# AAS_module_Power-rev1_2.net
KiCad netlist of a schematic drawn in Altium Designer
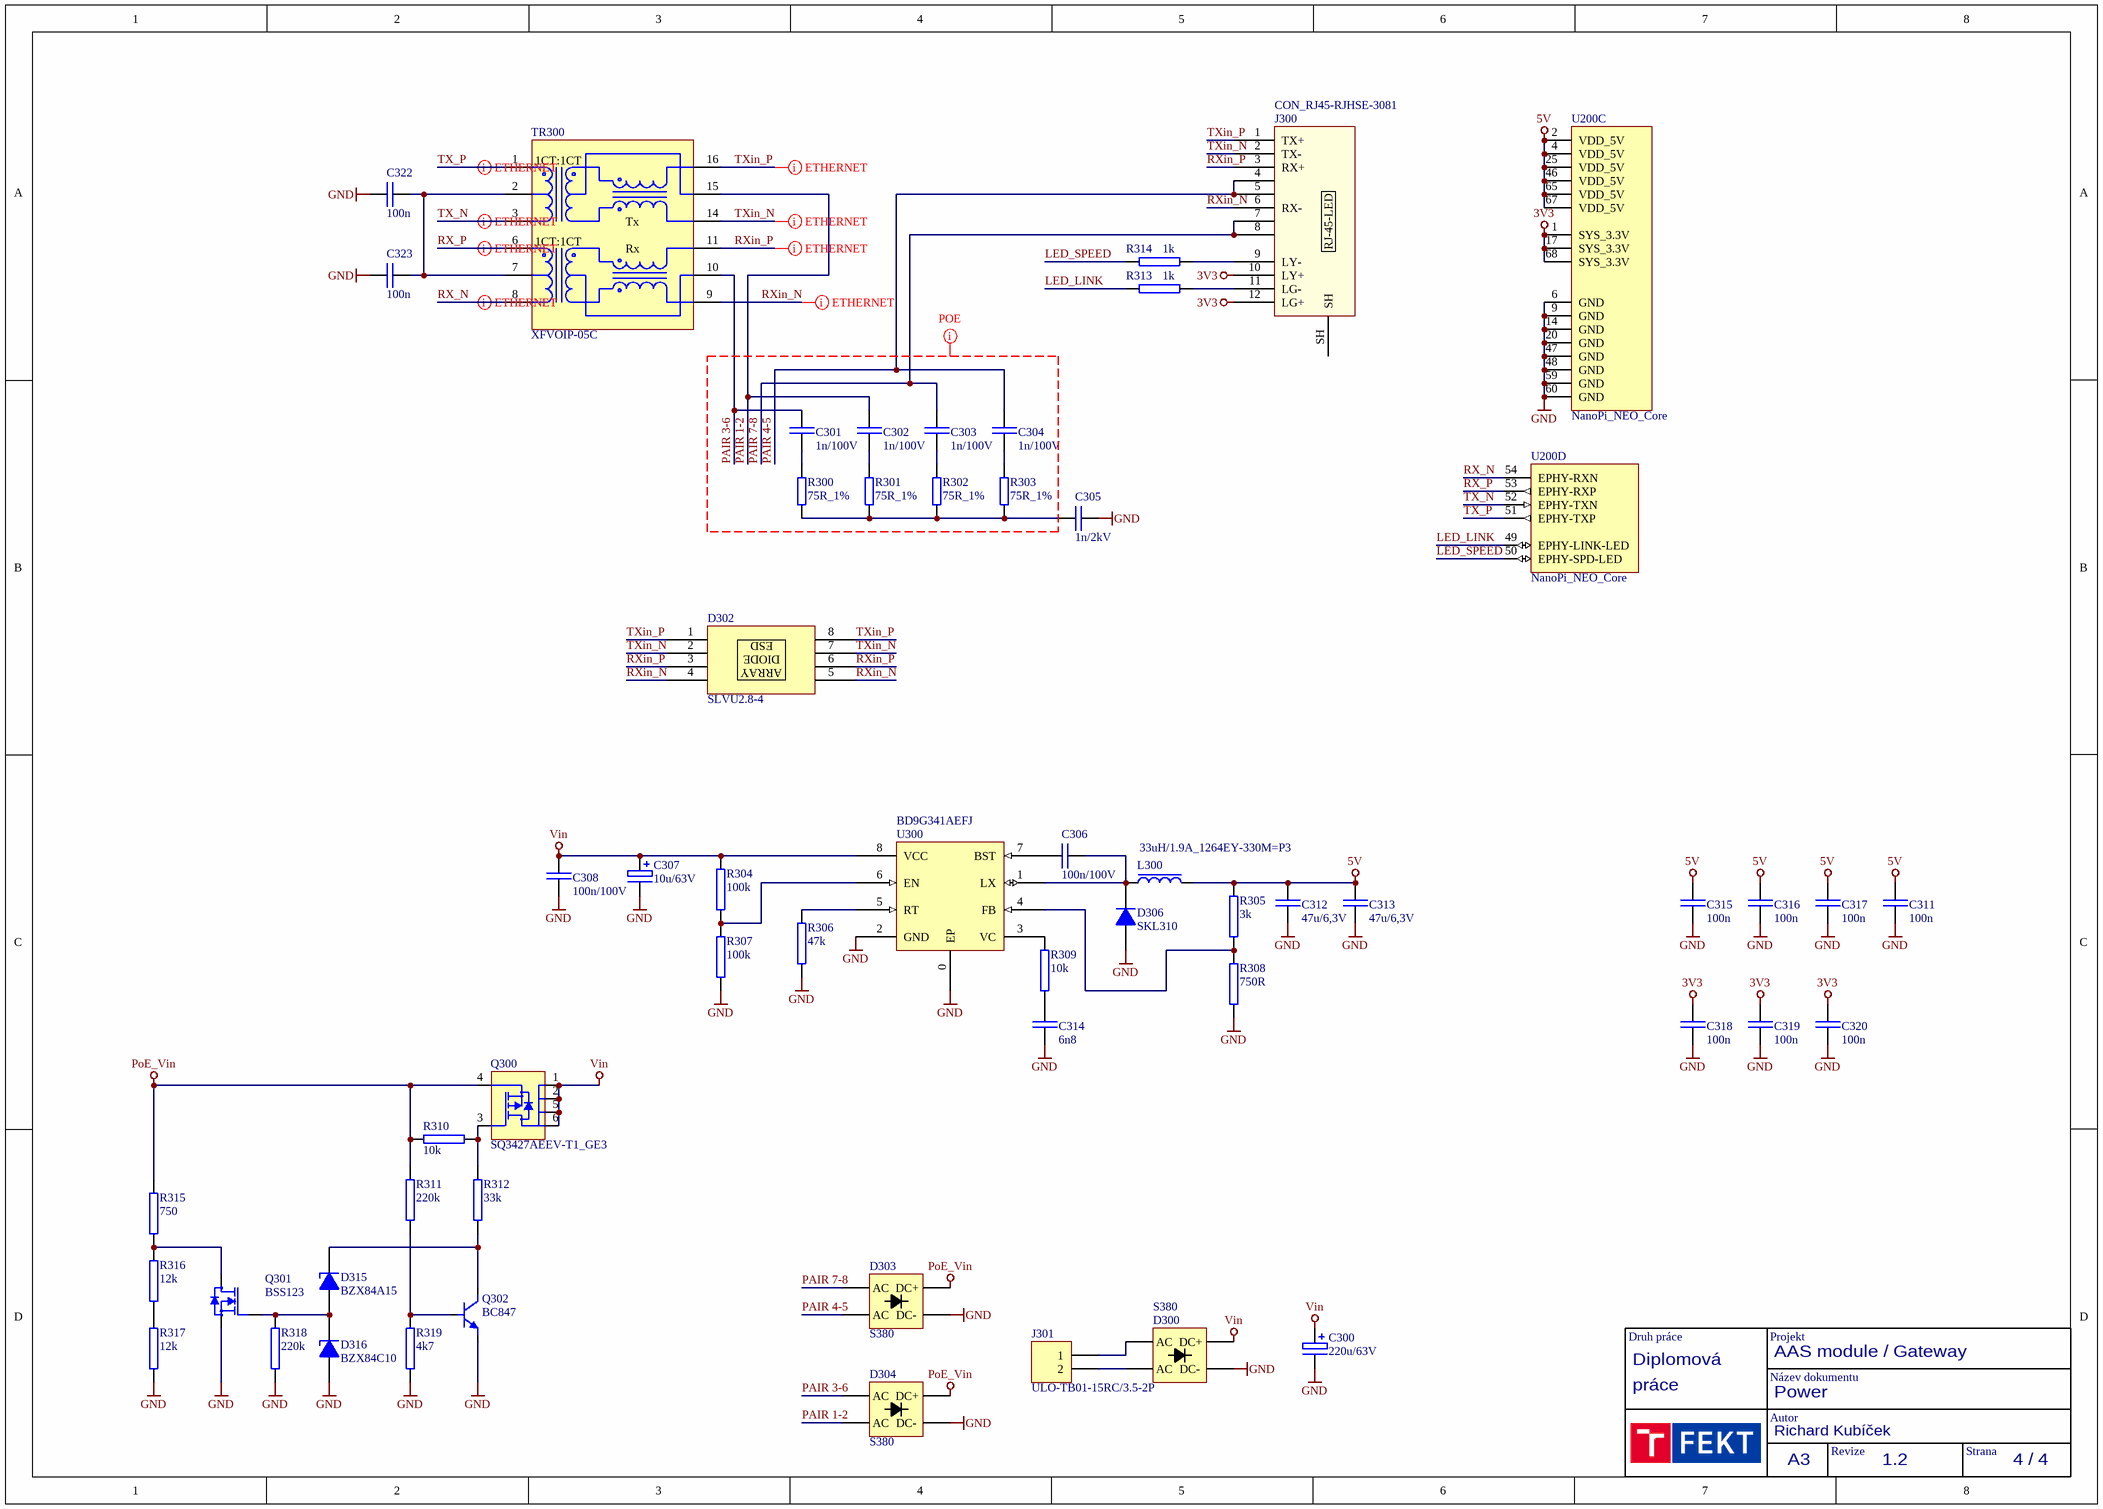
[diagram p0: AAS_module_Power-rev1_2.SchDoc]

(export (version "E")
  (design (tool "Eeschema 10.0.6"))
  (components
    (comp (ref "C300")
      (value "220u/63V")
      (footprint "CAP_D10xL20_P5_HR")
      (description "Electrolytic Capacitor")
      (libsource (lib "my_parts") (part "C_ELYT"))
    )
    (comp (ref "C301")
      (value "1n/100V")
      (footprint "C0603")
      (description "Capacitor SMD 0603")
      (libsource (lib "SmartSys") (part "C_0603"))
    )
    (comp (ref "C302")
      (value "1n/100V")
      (footprint "C0603")
      (description "Capacitor SMD 0603")
      (libsource (lib "SmartSys") (part "C_0603"))
    )
    (comp (ref "C303")
      (value "1n/100V")
      (footprint "C0603")
      (description "Capacitor SMD 0603")
      (libsource (lib "SmartSys") (part "C_0603"))
    )
    (comp (ref "C304")
      (value "1n/100V")
      (footprint "C0603")
      (description "Capacitor SMD 0603")
      (libsource (lib "SmartSys") (part "C_0603"))
    )
    (comp (ref "C305")
      (value "1n/2kV")
      (footprint "C1206")
      (description "Capacitor SMD 1206")
      (libsource (lib "SmartSys") (part "C_1206"))
    )
    (comp (ref "C306")
      (value "100n/100V")
      (footprint "C1206")
      (description "Capacitor SMD 1206")
      (libsource (lib "SmartSys") (part "C_1206"))
    )
    (comp (ref "C307")
      (value "10u/63V")
      (footprint "C_ALU_D6x5.8")
      (description "Electrolytic Aluminium Capacitor")
      (libsource (lib "SmartSys") (part "C_ALU"))
    )
    (comp (ref "C308")
      (value "100n/100V")
      (footprint "C1206")
      (description "Capacitor SMD 1206")
      (libsource (lib "SmartSys") (part "C_1206"))
    )
    (comp (ref "C311")
      (value "100n")
      (footprint "C0603")
      (description "Capacitor SMD 0603")
      (libsource (lib "SmartSys") (part "C_0603"))
    )
    (comp (ref "C312")
      (value "47u/6,3V")
      (footprint "C1206")
      (description "Capacitor SMD 1206")
      (libsource (lib "SmartSys") (part "C_1206"))
    )
    (comp (ref "C313")
      (value "47u/6,3V")
      (footprint "C1206")
      (description "Capacitor SMD 1206")
      (libsource (lib "SmartSys") (part "C_1206"))
    )
    (comp (ref "C314")
      (value "6n8")
      (footprint "C0805")
      (description "Capacitor SMD 0805")
      (libsource (lib "SmartSys") (part "C_0805"))
    )
    (comp (ref "C315")
      (value "100n")
      (footprint "C0603")
      (description "Capacitor SMD 0603")
      (libsource (lib "SmartSys") (part "C_0603"))
    )
    (comp (ref "C316")
      (value "100n")
      (footprint "C0603")
      (description "Capacitor SMD 0603")
      (libsource (lib "SmartSys") (part "C_0603"))
    )
    (comp (ref "C317")
      (value "100n")
      (footprint "C0603")
      (description "Capacitor SMD 0603")
      (libsource (lib "SmartSys") (part "C_0603"))
    )
    (comp (ref "C318")
      (value "100n")
      (footprint "C0603")
      (description "Capacitor SMD 0603")
      (libsource (lib "SmartSys") (part "C_0603"))
    )
    (comp (ref "C319")
      (value "100n")
      (footprint "C0603")
      (description "Capacitor SMD 0603")
      (libsource (lib "SmartSys") (part "C_0603"))
    )
    (comp (ref "C320")
      (value "100n")
      (footprint "C0603")
      (description "Capacitor SMD 0603")
      (libsource (lib "SmartSys") (part "C_0603"))
    )
    (comp (ref "C322")
      (value "100n")
      (footprint "C0603")
      (description "Capacitor SMD 0603")
      (libsource (lib "SmartSys") (part "C_0603"))
    )
    (comp (ref "C323")
      (value "100n")
      (footprint "C0603")
      (description "Capacitor SMD 0603")
      (libsource (lib "SmartSys") (part "C_0603"))
    )
    (comp (ref "D300")
      (value "S380")
      (footprint "MBS")
      (description "Diode rectifier")
      (libsource (lib "SmartSys") (part "_DIODE_BRIDGE_RECTIFIER"))
    )
    (comp (ref "D302")
      (value "SLVU2.8-4")
      (footprint "SO-8")
      (description "EPD TVS Diode Array  For ESD and Latch-Up Protection")
      (libsource (lib "SmartSys") (part "SLVU2.8-4"))
    )
    (comp (ref "D303")
      (value "S380")
      (footprint "MBS")
      (description "Diode rectifier")
      (libsource (lib "SmartSys") (part "_DIODE_BRIDGE_RECTIFIER"))
    )
    (comp (ref "D304")
      (value "S380")
      (footprint "MBS")
      (description "Diode rectifier")
      (libsource (lib "SmartSys") (part "_DIODE_BRIDGE_RECTIFIER"))
    )
    (comp (ref "D306")
      (value "SKL310")
      (footprint "SOD123")
      (description "Diode")
      (libsource (lib "SmartSys") (part "1N4007"))
    )
    (comp (ref "D315")
      (value "BZX84A15")
      (footprint "SOT-23")
      (description "Zener diode")
      (libsource (lib "SmartSys") (part "BZX84CXXX"))
    )
    (comp (ref "D316")
      (value "BZX84C10")
      (footprint "SOT-23")
      (description "Zener diode")
      (libsource (lib "SmartSys") (part "BZX84CXXX"))
    )
    (comp (ref "J300")
      (value "CON_RJ45-RJHSE-3081")
      (footprint "RJHSE-3081")
      (libsource (lib "my_parts") (part "CON_RJ45-LED_DESCRIPTION"))
    )
    (comp (ref "J301")
      (value "ULO-TB01-15RC/3.5-2P")
      (footprint "ULO-TB01-15VC-3.5-2P")
      (description "Connector 15EDG pitch 3.5mm Right Angle")
      (libsource (lib "SmartSys") (part "CON_ULO-TB01-15RC/3.5-2P"))
    )
    (comp (ref "L300")
      (value "33uH/1.9A_1264EY-330M=P3")
      (footprint "L_MURATA-DG6050C")
      (libsource (lib "ELEKON") (part "INDUCTOR"))
    )
    (comp (ref "Q300")
      (value "SQ3427AEEV-T1_GE3")
      (footprint "SOT-23-6")
      (libsource (lib "ELEKON") (part "SQ3419EV"))
    )
    (comp (ref "Q301")
      (value "BSS123")
      (footprint "SOT-23")
      (description "N-Channel MOSFET")
      (libsource (lib "SmartSys") (part "BSS138"))
    )
    (comp (ref "Q302")
      (value "BC847")
      (footprint "SOT-23")
      (description "NPN Transistor")
      (libsource (lib "SmartSys") (part "BC847"))
    )
    (comp (ref "R300")
      (value "75R_1%")
      (footprint "R_0805")
      (fields (field (name "TOLERANCE") "1"))
      (libsource (lib "ELEKON") (part "Resistor"))
    )
    (comp (ref "R301")
      (value "75R_1%")
      (footprint "R_0805")
      (fields (field (name "TOLERANCE") "1"))
      (libsource (lib "ELEKON") (part "Resistor"))
    )
    (comp (ref "R302")
      (value "75R_1%")
      (footprint "R_0805")
      (fields (field (name "TOLERANCE") "1"))
      (libsource (lib "ELEKON") (part "Resistor"))
    )
    (comp (ref "R303")
      (value "75R_1%")
      (footprint "R_0805")
      (fields (field (name "TOLERANCE") "1"))
      (libsource (lib "ELEKON") (part "Resistor"))
    )
    (comp (ref "R304")
      (value "100k")
      (footprint "R0603")
      (description "Resistor SMD 0603")
      (libsource (lib "SmartSys") (part "R_0603"))
    )
    (comp (ref "R305")
      (value "3k")
      (footprint "R0603")
      (description "Resistor SMD 0603")
      (libsource (lib "SmartSys") (part "R_0603"))
    )
    (comp (ref "R306")
      (value "47k")
      (footprint "R0603")
      (description "Resistor SMD 0603")
      (libsource (lib "SmartSys") (part "R_0603"))
    )
    (comp (ref "R307")
      (value "100k")
      (footprint "R0603")
      (description "Resistor SMD 0603")
      (libsource (lib "SmartSys") (part "R_0603"))
    )
    (comp (ref "R308")
      (value "750R")
      (footprint "R0603")
      (description "Resistor SMD 0603")
      (libsource (lib "SmartSys") (part "R_0603"))
    )
    (comp (ref "R309")
      (value "10k")
      (footprint "R0603")
      (description "Resistor SMD 0603")
      (libsource (lib "SmartSys") (part "R_0603"))
    )
    (comp (ref "R310")
      (value "10k")
      (footprint "R0603")
      (description "Resistor SMD 0603")
      (libsource (lib "SmartSys") (part "R_0603"))
    )
    (comp (ref "R311")
      (value "220k")
      (footprint "R0603")
      (description "Resistor SMD 0603")
      (libsource (lib "SmartSys") (part "R_0603"))
    )
    (comp (ref "R312")
      (value "33k")
      (footprint "R0603")
      (description "Resistor SMD 0603")
      (libsource (lib "SmartSys") (part "R_0603"))
    )
    (comp (ref "R313")
      (value "1k")
      (footprint "R0603")
      (description "Resistor SMD 0603")
      (libsource (lib "SmartSys") (part "R_0603"))
    )
    (comp (ref "R314")
      (value "1k")
      (footprint "R0603")
      (description "Resistor SMD 0603")
      (libsource (lib "SmartSys") (part "R_0603"))
    )
    (comp (ref "R315")
      (value "750")
      (footprint "R0603")
      (description "Resistor SMD 0603")
      (libsource (lib "SmartSys") (part "R_0603"))
    )
    (comp (ref "R316")
      (value "12k")
      (footprint "R0603")
      (description "Resistor SMD 0603")
      (libsource (lib "SmartSys") (part "R_0603"))
    )
    (comp (ref "R317")
      (value "12k")
      (footprint "R0603")
      (description "Resistor SMD 0603")
      (libsource (lib "SmartSys") (part "R_0603"))
    )
    (comp (ref "R318")
      (value "220k")
      (footprint "R0603")
      (description "Resistor SMD 0603")
      (libsource (lib "SmartSys") (part "R_0603"))
    )
    (comp (ref "R319")
      (value "4k7")
      (footprint "R0603")
      (description "Resistor SMD 0603")
      (libsource (lib "SmartSys") (part "R_0603"))
    )
    (comp (ref "TR300")
      (value "XFVOIP-05C")
      (footprint "XFVOIP-05")
      (description "LAN magnetics with filter")
      (libsource (lib "my_parts") (part "XFVOIP-05"))
    )
    (comp (ref "U200")
      (value "NanoPi_NEO_Core")
      (footprint "NanoPi_NEO_Core_right")
      (libsource (lib "my_parts") (part "NanoPi_NEO_Core"))
    )
    (comp (ref "U300")
      (value "BD9G341AEFJ")
      (footprint "SO-8_EP")
      (description "12V to 76V input voltage range 3A output current")
      (libsource (lib "my_parts") (part "BD9G341AEFJ"))
    )
  )
  (nets
    (net (code "1") (name "/LED_LINK") (class "Default")
      (node (ref "R313") (pin "2") (pinfunction "2_2") (pintype "passive"))
      (node (ref "U200") (pin "49") (pinfunction "EPHY-LINK-LED_49") (pintype "bidirectional"))
    )
    (net (code "2") (name "/LED_SPEED") (class "Default")
      (node (ref "R314") (pin "2") (pinfunction "2_2") (pintype "passive"))
      (node (ref "U200") (pin "50") (pinfunction "EPHY-SPD-LED_50") (pintype "bidirectional"))
    )
    (net (code "3") (name "/PAIR 1-2") (class "Default")
      (node (ref "C302") (pin "1") (pinfunction "1_1") (pintype "passive"))
      (node (ref "D304") (pin "4") (pinfunction "AC_4") (pintype "passive"))
      (node (ref "TR300") (pin "15") (pinfunction "TXCT_15") (pintype "passive"))
    )
    (net (code "4") (name "/PAIR 3-6") (class "Default")
      (node (ref "C301") (pin "1") (pinfunction "1_1") (pintype "passive"))
      (node (ref "D304") (pin "3") (pinfunction "AC_3") (pintype "passive"))
      (node (ref "TR300") (pin "10") (pinfunction "RXCT_10") (pintype "passive"))
    )
    (net (code "5") (name "/PAIR 4-5") (class "Default")
      (node (ref "C304") (pin "1") (pinfunction "1_1") (pintype "passive"))
      (node (ref "D303") (pin "4") (pinfunction "AC_4") (pintype "passive"))
      (node (ref "J300") (pin "4") (pintype "passive"))
      (node (ref "J300") (pin "5") (pintype "passive"))
    )
    (net (code "6") (name "/PAIR 7-8") (class "Default")
      (node (ref "C303") (pin "1") (pinfunction "1_1") (pintype "passive"))
      (node (ref "D303") (pin "3") (pinfunction "AC_3") (pintype "passive"))
      (node (ref "J300") (pin "7") (pintype "passive"))
      (node (ref "J300") (pin "8") (pintype "passive"))
    )
    (net (code "7") (name "/RX_N") (class "Default")
      (node (ref "TR300") (pin "8") (pinfunction "RD-_8") (pintype "passive"))
      (node (ref "U200") (pin "54") (pinfunction "EPHY-RXN_54") (pintype "passive"))
    )
    (net (code "8") (name "/RX_P") (class "Default")
      (node (ref "TR300") (pin "6") (pinfunction "RD+_6") (pintype "passive"))
      (node (ref "U200") (pin "53") (pinfunction "EPHY-RXP_53") (pintype "output"))
    )
    (net (code "9") (name "/RXin_N") (class "Default")
      (node (ref "D302") (pin "4") (pinfunction "4_4") (pintype "passive"))
      (node (ref "D302") (pin "5") (pinfunction "5_5") (pintype "passive"))
      (node (ref "J300") (pin "6") (pinfunction "RX-_6") (pintype "passive"))
      (node (ref "TR300") (pin "9") (pinfunction "RX1-_9") (pintype "passive"))
    )
    (net (code "10") (name "/RXin_P") (class "Default")
      (node (ref "D302") (pin "3") (pinfunction "3_3") (pintype "passive"))
      (node (ref "D302") (pin "6") (pinfunction "6_6") (pintype "passive"))
      (node (ref "J300") (pin "3") (pinfunction "RX+_3") (pintype "passive"))
      (node (ref "TR300") (pin "11") (pinfunction "RX1+_11") (pintype "passive"))
    )
    (net (code "11") (name "/TX_N") (class "Default")
      (node (ref "TR300") (pin "3") (pinfunction "TD-_3") (pintype "passive"))
      (node (ref "U200") (pin "52") (pinfunction "EPHY-TXN_52") (pintype "input"))
    )
    (net (code "12") (name "/TX_P") (class "Default")
      (node (ref "TR300") (pin "1") (pinfunction "TD+_1") (pintype "passive"))
      (node (ref "U200") (pin "51") (pinfunction "EPHY-TXP_51") (pintype "output"))
    )
    (net (code "13") (name "/TXin_N") (class "Default")
      (node (ref "D302") (pin "2") (pinfunction "2_2") (pintype "passive"))
      (node (ref "D302") (pin "7") (pinfunction "7_7") (pintype "passive"))
      (node (ref "J300") (pin "2") (pinfunction "TX-_2") (pintype "passive"))
      (node (ref "TR300") (pin "14") (pinfunction "TX1-_14") (pintype "passive"))
    )
    (net (code "14") (name "/TXin_P") (class "Default")
      (node (ref "D302") (pin "1") (pinfunction "1_1") (pintype "passive"))
      (node (ref "D302") (pin "8") (pinfunction "8_8") (pintype "passive"))
      (node (ref "J300") (pin "1") (pinfunction "TX+_1") (pintype "passive"))
      (node (ref "TR300") (pin "16") (pinfunction "TX1+_16") (pintype "passive"))
    )
    (net (code "15") (name "3V3") (class "Default")
      (node (ref "C318") (pin "1") (pinfunction "1_1") (pintype "passive"))
      (node (ref "C319") (pin "1") (pinfunction "1_1") (pintype "passive"))
      (node (ref "C320") (pin "1") (pinfunction "1_1") (pintype "passive"))
      (node (ref "J300") (pin "10") (pinfunction "LY+_10") (pintype "passive"))
      (node (ref "J300") (pin "12") (pinfunction "LG+_12") (pintype "passive"))
      (node (ref "U200") (pin "1") (pinfunction "SYS_3.3V_1") (pintype "power_in"))
      (node (ref "U200") (pin "17") (pinfunction "SYS_3.3V_17") (pintype "power_in"))
      (node (ref "U200") (pin "68") (pinfunction "SYS_3.3V_68") (pintype "power_in"))
    )
    (net (code "16") (name "5V") (class "Default")
      (node (ref "C311") (pin "1") (pinfunction "1_1") (pintype "passive"))
      (node (ref "C312") (pin "1") (pinfunction "1_1") (pintype "passive"))
      (node (ref "C313") (pin "1") (pinfunction "1_1") (pintype "passive"))
      (node (ref "C315") (pin "1") (pinfunction "1_1") (pintype "passive"))
      (node (ref "C316") (pin "1") (pinfunction "1_1") (pintype "passive"))
      (node (ref "C317") (pin "1") (pinfunction "1_1") (pintype "passive"))
      (node (ref "L300") (pin "2") (pinfunction "2_2") (pintype "passive"))
      (node (ref "R305") (pin "2") (pinfunction "2_2") (pintype "passive"))
      (node (ref "U200") (pin "2") (pinfunction "VDD_5V_2") (pintype "power_in"))
      (node (ref "U200") (pin "25") (pinfunction "VDD_5V_25") (pintype "power_in"))
      (node (ref "U200") (pin "4") (pinfunction "VDD_5V_4") (pintype "power_in"))
      (node (ref "U200") (pin "46") (pinfunction "VDD_5V_46") (pintype "power_in"))
      (node (ref "U200") (pin "65") (pinfunction "VDD_5V_65") (pintype "power_in"))
      (node (ref "U200") (pin "67") (pinfunction "VDD_5V_67") (pintype "power_in"))
    )
    (net (code "17") (name "GND") (class "Default")
      (node (ref "C300") (pin "2") (pinfunction "-_2") (pintype "passive"))
      (node (ref "C305") (pin "2") (pinfunction "2_2") (pintype "passive"))
      (node (ref "C307") (pin "2") (pinfunction "-_2") (pintype "passive"))
      (node (ref "C308") (pin "2") (pinfunction "2_2") (pintype "passive"))
      (node (ref "C311") (pin "2") (pinfunction "2_2") (pintype "passive"))
      (node (ref "C312") (pin "2") (pinfunction "2_2") (pintype "passive"))
      (node (ref "C313") (pin "2") (pinfunction "2_2") (pintype "passive"))
      (node (ref "C314") (pin "1") (pinfunction "1_1") (pintype "passive"))
      (node (ref "C315") (pin "2") (pinfunction "2_2") (pintype "passive"))
      (node (ref "C316") (pin "2") (pinfunction "2_2") (pintype "passive"))
      (node (ref "C317") (pin "2") (pinfunction "2_2") (pintype "passive"))
      (node (ref "C318") (pin "2") (pinfunction "2_2") (pintype "passive"))
      (node (ref "C319") (pin "2") (pinfunction "2_2") (pintype "passive"))
      (node (ref "C320") (pin "2") (pinfunction "2_2") (pintype "passive"))
      (node (ref "C322") (pin "1") (pinfunction "1_1") (pintype "passive"))
      (node (ref "C323") (pin "1") (pinfunction "1_1") (pintype "passive"))
      (node (ref "D300") (pin "2") (pinfunction "DC-_2") (pintype "passive"))
      (node (ref "D303") (pin "2") (pinfunction "DC-_2") (pintype "passive"))
      (node (ref "D304") (pin "2") (pinfunction "DC-_2") (pintype "passive"))
      (node (ref "D306") (pin "A") (pinfunction "A_A") (pintype "passive"))
      (node (ref "D316") (pin "A") (pinfunction "A_A") (pintype "passive"))
      (node (ref "Q301") (pin "S") (pinfunction "S_S") (pintype "passive"))
      (node (ref "Q302") (pin "E") (pinfunction "E_E") (pintype "passive"))
      (node (ref "R306") (pin "1") (pinfunction "1_1") (pintype "passive"))
      (node (ref "R307") (pin "1") (pinfunction "1_1") (pintype "passive"))
      (node (ref "R308") (pin "1") (pinfunction "1_1") (pintype "passive"))
      (node (ref "R317") (pin "1") (pinfunction "1_1") (pintype "passive"))
      (node (ref "R318") (pin "1") (pinfunction "1_1") (pintype "passive"))
      (node (ref "R319") (pin "1") (pinfunction "1_1") (pintype "passive"))
      (node (ref "U200") (pin "14") (pinfunction "GND_14") (pintype "power_in"))
      (node (ref "U200") (pin "20") (pinfunction "GND_20") (pintype "power_in"))
      (node (ref "U200") (pin "47") (pinfunction "GND_47") (pintype "power_in"))
      (node (ref "U200") (pin "48") (pinfunction "GND_48") (pintype "power_in"))
      (node (ref "U200") (pin "59") (pinfunction "GND_59") (pintype "power_in"))
      (node (ref "U200") (pin "6") (pinfunction "GND_6") (pintype "power_in"))
      (node (ref "U200") (pin "60") (pinfunction "GND_60") (pintype "power_in"))
      (node (ref "U200") (pin "9") (pinfunction "GND_9") (pintype "power_in"))
      (node (ref "U300") (pin "0") (pinfunction "EP_0") (pintype "passive"))
      (node (ref "U300") (pin "2") (pinfunction "GND_2") (pintype "passive"))
    )
    (net (code "18") (name "Net-(C301-Pad2)") (class "Default")
      (node (ref "C301") (pin "2") (pinfunction "2_2") (pintype "passive"))
      (node (ref "R300") (pin "2") (pinfunction "2_2") (pintype "passive"))
    )
    (net (code "19") (name "Net-(C302-Pad2)") (class "Default")
      (node (ref "C302") (pin "2") (pinfunction "2_2") (pintype "passive"))
      (node (ref "R301") (pin "2") (pinfunction "2_2") (pintype "passive"))
    )
    (net (code "20") (name "Net-(C303-Pad2)") (class "Default")
      (node (ref "C303") (pin "2") (pinfunction "2_2") (pintype "passive"))
      (node (ref "R302") (pin "2") (pinfunction "2_2") (pintype "passive"))
    )
    (net (code "21") (name "Net-(C304-Pad2)") (class "Default")
      (node (ref "C304") (pin "2") (pinfunction "2_2") (pintype "passive"))
      (node (ref "R303") (pin "2") (pinfunction "2_2") (pintype "passive"))
    )
    (net (code "22") (name "Net-(C305-Pad1)") (class "Default")
      (node (ref "C305") (pin "1") (pinfunction "1_1") (pintype "passive"))
      (node (ref "R300") (pin "1") (pinfunction "1_1") (pintype "passive"))
      (node (ref "R301") (pin "1") (pinfunction "1_1") (pintype "passive"))
      (node (ref "R302") (pin "1") (pinfunction "1_1") (pintype "passive"))
      (node (ref "R303") (pin "1") (pinfunction "1_1") (pintype "passive"))
    )
    (net (code "23") (name "Net-(C314-Pad2)") (class "Default")
      (node (ref "C314") (pin "2") (pinfunction "2_2") (pintype "passive"))
      (node (ref "R309") (pin "1") (pinfunction "1_1") (pintype "passive"))
    )
    (net (code "24") (name "Net-(D300-AC-Pad3)") (class "Default")
      (node (ref "D300") (pin "3") (pinfunction "AC_3") (pintype "passive"))
      (node (ref "J301") (pin "1") (pinfunction "1_1") (pintype "passive"))
    )
    (net (code "25") (name "Net-(D300-AC-Pad4)") (class "Default")
      (node (ref "D300") (pin "4") (pinfunction "AC_4") (pintype "passive"))
      (node (ref "J301") (pin "2") (pinfunction "2_2") (pintype "passive"))
    )
    (net (code "26") (name "Net-(D315-PadA)") (class "Default")
      (node (ref "D315") (pin "A") (pinfunction "A_A") (pintype "passive"))
      (node (ref "D316") (pin "K") (pinfunction "K_K") (pintype "passive"))
      (node (ref "Q301") (pin "G") (pinfunction "G_G") (pintype "passive"))
      (node (ref "R318") (pin "2") (pinfunction "2_2") (pintype "passive"))
    )
    (net (code "27") (name "Net-(D315-PadK)") (class "Default")
      (node (ref "D315") (pin "K") (pinfunction "K_K") (pintype "passive"))
      (node (ref "Q302") (pin "C") (pinfunction "C_C") (pintype "passive"))
      (node (ref "R312") (pin "1") (pinfunction "1_1") (pintype "passive"))
    )
    (net (code "28") (name "Net-(J300-LG-)") (class "Default")
      (node (ref "J300") (pin "11") (pinfunction "LG-_11") (pintype "passive"))
      (node (ref "R313") (pin "1") (pinfunction "1_1") (pintype "passive"))
    )
    (net (code "29") (name "Net-(J300-LY-)") (class "Default")
      (node (ref "J300") (pin "9") (pinfunction "LY-_9") (pintype "passive"))
      (node (ref "R314") (pin "1") (pinfunction "1_1") (pintype "passive"))
    )
    (net (code "30") (name "Net-(Q300-G)") (class "Default")
      (node (ref "Q300") (pin "3") (pinfunction "G_3") (pintype "passive"))
      (node (ref "R310") (pin "1") (pinfunction "1_1") (pintype "passive"))
      (node (ref "R312") (pin "2") (pinfunction "2_2") (pintype "passive"))
    )
    (net (code "31") (name "Net-(Q301-PadD)") (class "Default")
      (node (ref "Q301") (pin "D") (pinfunction "D_D") (pintype "passive"))
      (node (ref "R315") (pin "1") (pinfunction "1_1") (pintype "passive"))
      (node (ref "R316") (pin "2") (pinfunction "2_2") (pintype "passive"))
    )
    (net (code "32") (name "Net-(Q302-PadB)") (class "Default")
      (node (ref "Q302") (pin "B") (pinfunction "B_B") (pintype "passive"))
      (node (ref "R311") (pin "1") (pinfunction "1_1") (pintype "passive"))
      (node (ref "R319") (pin "2") (pinfunction "2_2") (pintype "passive"))
    )
    (net (code "33") (name "Net-(R316-Pad1)") (class "Default")
      (node (ref "R316") (pin "1") (pinfunction "1_1") (pintype "passive"))
      (node (ref "R317") (pin "2") (pinfunction "2_2") (pintype "passive"))
    )
    (net (code "34") (name "Net-(TR300-RCT)") (class "Default")
      (node (ref "C322") (pin "2") (pinfunction "2_2") (pintype "passive"))
      (node (ref "C323") (pin "2") (pinfunction "2_2") (pintype "passive"))
      (node (ref "TR300") (pin "2") (pinfunction "TCT_2") (pintype "passive"))
      (node (ref "TR300") (pin "7") (pinfunction "RCT_7") (pintype "passive"))
    )
    (net (code "35") (name "Net-(U300-BST)") (class "Default")
      (node (ref "C306") (pin "1") (pinfunction "1_1") (pintype "passive"))
      (node (ref "U300") (pin "7") (pinfunction "BST_7") (pintype "input"))
    )
    (net (code "36") (name "Net-(U300-EN)") (class "Default")
      (node (ref "R304") (pin "1") (pinfunction "1_1") (pintype "passive"))
      (node (ref "R307") (pin "2") (pinfunction "2_2") (pintype "passive"))
      (node (ref "U300") (pin "6") (pinfunction "EN_6") (pintype "input"))
    )
    (net (code "37") (name "Net-(U300-FB)") (class "Default")
      (node (ref "R305") (pin "1") (pinfunction "1_1") (pintype "passive"))
      (node (ref "R308") (pin "2") (pinfunction "2_2") (pintype "passive"))
      (node (ref "U300") (pin "4") (pinfunction "FB_4") (pintype "input"))
    )
    (net (code "38") (name "Net-(U300-LX)") (class "Default")
      (node (ref "C306") (pin "2") (pinfunction "2_2") (pintype "passive"))
      (node (ref "D306") (pin "K") (pinfunction "K_K") (pintype "passive"))
      (node (ref "L300") (pin "1") (pinfunction "1_1") (pintype "passive"))
      (node (ref "U300") (pin "1") (pinfunction "LX_1") (pintype "bidirectional"))
    )
    (net (code "39") (name "Net-(U300-RT)") (class "Default")
      (node (ref "R306") (pin "2") (pinfunction "2_2") (pintype "passive"))
      (node (ref "U300") (pin "5") (pinfunction "RT_5") (pintype "input"))
    )
    (net (code "40") (name "Net-(U300-VC)") (class "Default")
      (node (ref "R309") (pin "2") (pinfunction "2_2") (pintype "passive"))
      (node (ref "U300") (pin "3") (pinfunction "VC_3") (pintype "passive"))
    )
    (net (code "41") (name "PoE_Vin") (class "Default")
      (node (ref "D303") (pin "1") (pinfunction "DC+_1") (pintype "passive"))
      (node (ref "D304") (pin "1") (pinfunction "DC+_1") (pintype "passive"))
      (node (ref "Q300") (pin "4") (pinfunction "S_4") (pintype "passive"))
      (node (ref "R310") (pin "2") (pinfunction "2_2") (pintype "passive"))
      (node (ref "R311") (pin "2") (pinfunction "2_2") (pintype "passive"))
      (node (ref "R315") (pin "2") (pinfunction "2_2") (pintype "passive"))
    )
    (net (code "42") (name "Vin") (class "Default")
      (node (ref "C300") (pin "1") (pinfunction "+_1") (pintype "passive"))
      (node (ref "C307") (pin "1") (pinfunction "+_1") (pintype "passive"))
      (node (ref "C308") (pin "1") (pinfunction "1_1") (pintype "passive"))
      (node (ref "D300") (pin "1") (pinfunction "DC+_1") (pintype "passive"))
      (node (ref "Q300") (pin "1") (pinfunction "D_1") (pintype "passive"))
      (node (ref "Q300") (pin "2") (pinfunction "D_2") (pintype "passive"))
      (node (ref "Q300") (pin "5") (pinfunction "D_5") (pintype "passive"))
      (node (ref "Q300") (pin "6") (pinfunction "D_6") (pintype "passive"))
      (node (ref "R304") (pin "2") (pinfunction "2_2") (pintype "passive"))
      (node (ref "U300") (pin "8") (pinfunction "VCC_8") (pintype "passive"))
    )
    (net (code "43") (name "unconnected-(J300-PadSH)") (class "Default")
      (node (ref "J300") (pin "SH") (pinfunction "SH_SH") (pintype "passive"))
    )
    (net (code "44") (name "unconnected-(TR300-NC-Pad4)") (class "Default")
      (node (ref "TR300") (pin "4") (pinfunction "NC_4") (pintype "passive"))
    )
    (net (code "45") (name "unconnected-(TR300-NC-Pad5)") (class "Default")
      (node (ref "TR300") (pin "5") (pinfunction "NC_5") (pintype "passive"))
    )
    (net (code "46") (name "unconnected-(TR300-NC-Pad12)") (class "Default")
      (node (ref "TR300") (pin "12") (pinfunction "NC_12") (pintype "passive"))
    )
    (net (code "47") (name "unconnected-(TR300-NC-Pad13)") (class "Default")
      (node (ref "TR300") (pin "13") (pinfunction "NC_13") (pintype "passive"))
    )
  )
)
